# Sheet1.net
KiCad netlist of a schematic drawn in Altium Designer
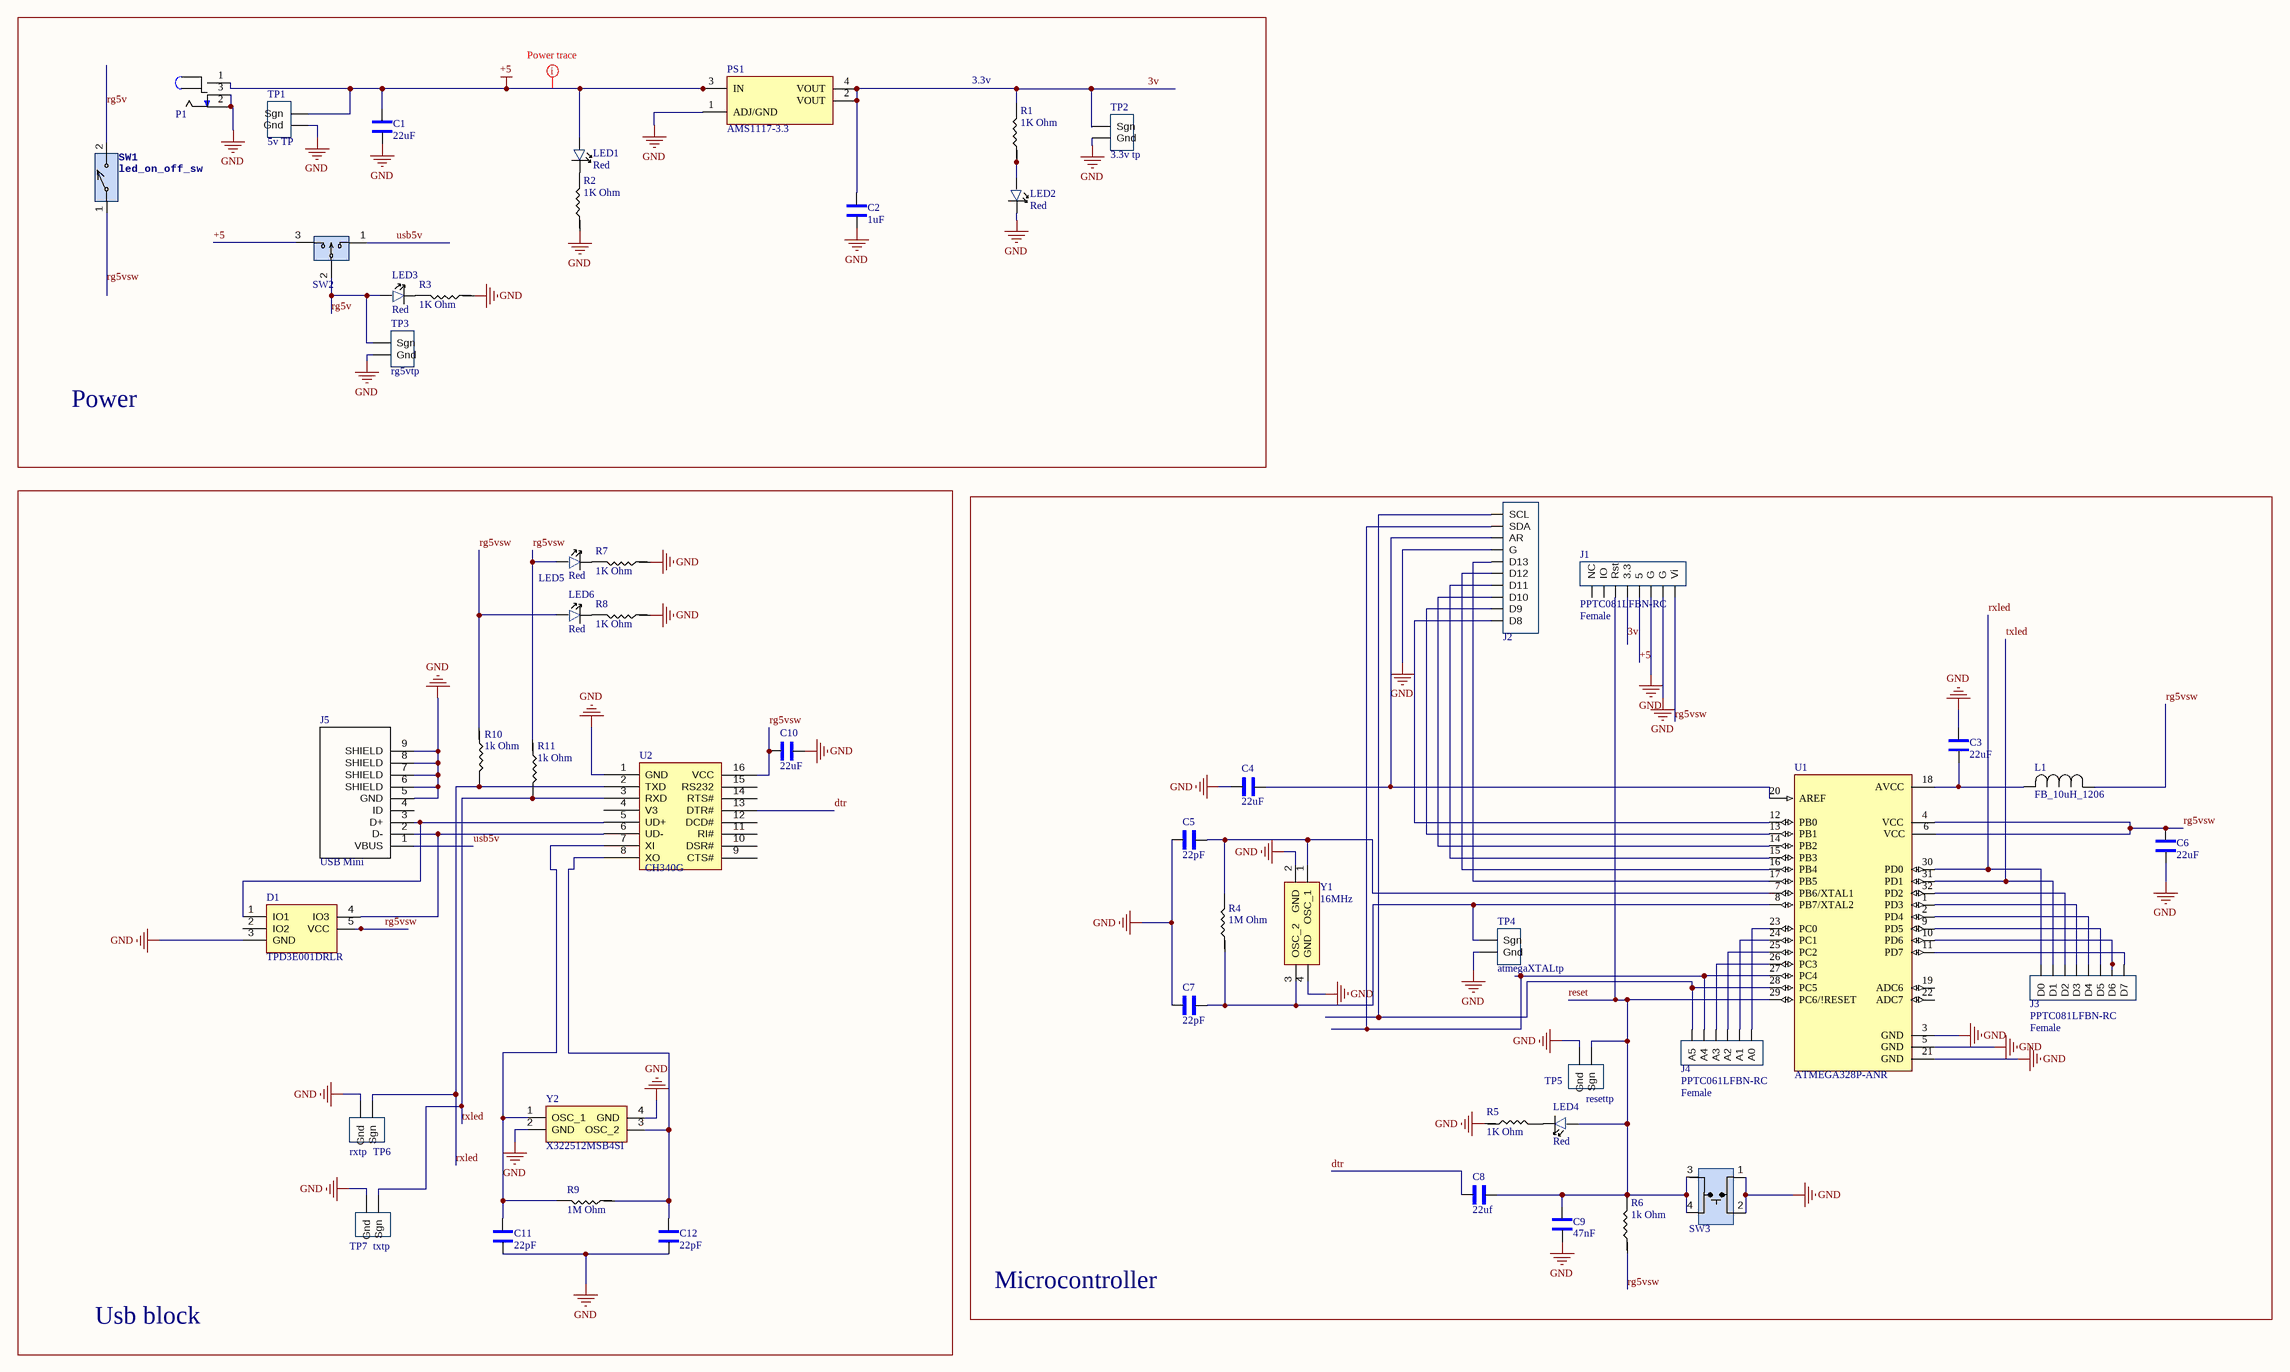
[diagram p0: Sheet1.SchDoc]

(export (version "E")
  (design (tool "Eeschema 10.0.6"))
  (components
    (comp (ref "C1")
      (value "22uF")
      (footprint "1206_Passive_Capacitor")
      (description "22uF ±10% 25V X5R 1206 Multilayer Ceramic Capacitors MLCC - SMD/SMT RoHS")
      (fields (field (name "MFR PART #") "CL31A226KAHNNNE") (field (name "LCSC PART#") "C12891"))
      (libsource (lib "ECEN5730Lib_2023_05_DS") (part "C_22uF_1206"))
    )
    (comp (ref "C2")
      (value "1uF")
      (footprint "1206_Passive_Capacitor")
      (description "MULTILAYER CERAMIC CAPACITORS MLCC - SMD/SMT 1UF 50V 1206 ROHS")
      (fields (field (name "MFR PART #") "CL31B105KBHNNNE") (field (name "LCSC PART#") "C1848"))
      (libsource (lib "ECEN5730Lib_2023_05_DS") (part "C_1uF_1206"))
    )
    (comp (ref "C3")
      (value "22uF")
      (footprint "1206_Passive_Capacitor")
      (description "22uF ±10% 25V X5R 1206 Multilayer Ceramic Capacitors MLCC - SMD/SMT RoHS")
      (fields (field (name "MFR PART #") "CL31A226KAHNNNE") (field (name "LCSC PART#") "C12891"))
      (libsource (lib "ECEN5730Lib_2023_05_DS") (part "C_22uF_1206"))
    )
    (comp (ref "C4")
      (value "22uF")
      (footprint "1206_Passive_Capacitor")
      (description "22uF ±10% 25V X5R 1206 Multilayer Ceramic Capacitors MLCC - SMD/SMT RoHS")
      (fields (field (name "MFR PART #") "CL31A226KAHNNNE") (field (name "LCSC PART#") "C12891"))
      (libsource (lib "ECEN5730Lib_2023_05_DS") (part "C_22uF_1206"))
    )
    (comp (ref "C5")
      (value "22pF")
      (footprint "1206_Passive_Capacitor")
      (description "22pF ±5% 1kV C0G 1206 Multilayer Ceramic Capacitors MLCC - SMD/SMT RoHS")
      (fields (field (name "LCSC PART#") "C107174") (field (name "MFR PART #") "CC1206JKNPOCBN220"))
      (libsource (lib "ECEN5730Lib_2023_05_DS") (part "C_22pF_1206"))
    )
    (comp (ref "C6")
      (value "22uF")
      (footprint "1206_Passive_Capacitor")
      (description "22uF ±10% 25V X5R 1206 Multilayer Ceramic Capacitors MLCC - SMD/SMT RoHS")
      (fields (field (name "MFR PART #") "CL31A226KAHNNNE") (field (name "LCSC PART#") "C12891"))
      (libsource (lib "ECEN5730Lib_2023_05_DS") (part "C_22uF_1206"))
    )
    (comp (ref "C7")
      (value "22pF")
      (footprint "1206_Passive_Capacitor")
      (description "22pF ±5% 1kV C0G 1206 Multilayer Ceramic Capacitors MLCC - SMD/SMT RoHS")
      (fields (field (name "LCSC PART#") "C107174") (field (name "MFR PART #") "CC1206JKNPOCBN220"))
      (libsource (lib "ECEN5730Lib_2023_05_DS") (part "C_22pF_1206"))
    )
    (comp (ref "C8")
      (value "22uf")
      (footprint "1206_Passive_Capacitor")
      (description "MULTILAYER CERAMIC CAPACITORS MLCC - SMD/SMT 1UF 50V 1206 ROHS")
      (fields (field (name "MFR PART #") "CL31B105KBHNNNE") (field (name "LCSC PART#") "C1848"))
      (libsource (lib "ECEN5730Lib_2023_05_DS") (part "C_1uF_1206"))
    )
    (comp (ref "C9")
      (value "47nF")
      (footprint "1206_Passive_Capacitor")
      (description "47nF ±5% 50V C0G 1206 Multilayer Ceramic Capacitors MLCC - SMD/SMT RoHS")
      (fields (field (name "LCSC PART#") "C21812") (field (name "MFR PART #") "GRM31M5C1H473JA01L"))
      (libsource (lib "ECEN5730Lib_2023_05_DS") (part "C_47nF_1206"))
    )
    (comp (ref "C10")
      (value "22uF")
      (footprint "1206_Passive_Capacitor")
      (description "22uF ±10% 25V X5R 1206 Multilayer Ceramic Capacitors MLCC - SMD/SMT RoHS")
      (fields (field (name "MFR PART #") "CL31A226KAHNNNE") (field (name "LCSC PART#") "C12891"))
      (libsource (lib "ECEN5730Lib_2023_05_DS") (part "C_22uF_1206"))
    )
    (comp (ref "C11")
      (value "22pF")
      (footprint "1206_Passive_Capacitor")
      (description "22pF ±5% 1kV C0G 1206 Multilayer Ceramic Capacitors MLCC - SMD/SMT RoHS")
      (fields (field (name "LCSC PART#") "C107174") (field (name "MFR PART #") "CC1206JKNPOCBN220"))
      (libsource (lib "ECEN5730Lib_2023_05_DS") (part "C_22pF_1206"))
    )
    (comp (ref "C12")
      (value "22pF")
      (footprint "1206_Passive_Capacitor")
      (description "22pF ±5% 1kV C0G 1206 Multilayer Ceramic Capacitors MLCC - SMD/SMT RoHS")
      (fields (field (name "LCSC PART#") "C107174") (field (name "MFR PART #") "CC1206JKNPOCBN220"))
      (libsource (lib "ECEN5730Lib_2023_05_DS") (part "C_22pF_1206"))
    )
    (comp (ref "D1")
      (value "TPD3E001DRLR")
      (footprint "SOTFL50P160X60-5N")
      (description "Low-Capacitance 3-Channel +/-15KV ESD-Protection Array for High-Speed Data Interfaces")
      (fields (field (name "MOUSER PART NUMBER") "595-TPD3E001DRLR"))
      (libsource (lib "TPD3E001DRLR") (part "TPD3E001DRLR"))
    )
    (comp (ref "J1")
      (value "PPTC081LFBN-RC")
      (footprint "8_PIN_ARD-PWR_100MIL")
      (description "8 Position Header Connector 0.100\" (2.54mm) Through Hole Tin")
      (fields (field (name "LCSC PART#") "C27438") (field (name "ALTIUM_VALUE") "Female"))
      (libsource (lib "ECEN5730Lib_2023_05_DS") (part "JF_8_PIN_FEMA_ARD-Pwr"))
    )
    (comp (ref "J2")
      (value "PPTC101LFBN-RC")
      (footprint "10_PIN_ARDUINO_100MIL")
      (description "10 Position Header Connector 0.100\" (2.54mm) Through Hole Tin")
      (fields (field (name "LCSC PART#") "C225507"))
      (libsource (lib "ECEN5730Lib_2023_05_DS") (part "JF_10_PIN_FEMA_ARDUINO"))
    )
    (comp (ref "J3")
      (value "PPTC081LFBN-RC")
      (footprint "8_PIN_ARD-DIG_100MIL")
      (description "8 Position Header Connector 0.100\" (2.54mm) Through Hole Tin")
      (fields (field (name "LCSC PART#") "C27438") (field (name "ALTIUM_VALUE") "Female"))
      (libsource (lib "ECEN5730Lib_2023_05_DS") (part "JF_8_PIN_FEMA_ARD-Dig"))
    )
    (comp (ref "J4")
      (value "PPTC061LFBN-RC")
      (footprint "6_PIN_ARD-Analog_100mil")
      (description "6 Position Header Connector 0.100\" (2.54mm) Through Hole Tin")
      (fields (field (name "LCSC PART#") "C40877") (field (name "ALTIUM_VALUE") "Female"))
      (libsource (lib "ECEN5730Lib_2023_05_DS") (part "JF_6_PIN_FEMA_ARD-Anolog"))
    )
    (comp (ref "J5")
      (value "USB Mini")
      (footprint "USB_MINI_B")
      (description "Through Hole USB Connectors RoHS")
      (fields (field (name "LCSC PART#") "C46398") (field (name "MFR PART #") "920-462A2021D10102"))
      (libsource (lib "ECEN5730Lib_2023_05_DS") (part "J_USB_B_Mini"))
    )
    (comp (ref "L1")
      (value "FB_10uH_1206")
      (footprint "AIML-1206_ABR-M")
      (description "25mA 10uH ±10% 800mΩ 1206  Inductors (SMD) ROHS")
      (fields (field (name "MFR PART #") "CMI321609X100KT") (field (name "LCSC PART#") "C1051"))
      (libsource (lib "ECEN5730Lib_2023_05_DS") (part "FB_10uH_1206"))
    )
    (comp (ref "LED1")
      (value "Red")
      (footprint "LED_1206")
      (description "Red 621~631nm 1206 Light Emitting Diodes (LED) RoHS")
      (fields (field (name "MFR PART #") "15-21/R6C-FQ1R1B/2T") (field (name "LCSC PART#") "C93133"))
      (libsource (lib "ECEN5730Lib_2023_05_DS") (part "LED_RED_1206"))
    )
    (comp (ref "LED2")
      (value "Red")
      (footprint "LED_1206")
      (description "Red 621~631nm 1206 Light Emitting Diodes (LED) RoHS")
      (fields (field (name "MFR PART #") "15-21/R6C-FQ1R1B/2T") (field (name "LCSC PART#") "C93133"))
      (libsource (lib "ECEN5730Lib_2023_05_DS") (part "LED_RED_1206"))
    )
    (comp (ref "LED3")
      (value "Red")
      (footprint "LED_1206")
      (description "Red 621~631nm 1206 Light Emitting Diodes (LED) RoHS")
      (fields (field (name "MFR PART #") "15-21/R6C-FQ1R1B/2T") (field (name "LCSC PART#") "C93133"))
      (libsource (lib "ECEN5730Lib_2023_05_DS") (part "LED_RED_1206"))
    )
    (comp (ref "LED4")
      (value "Red")
      (footprint "LED_1206")
      (description "Red 621~631nm 1206 Light Emitting Diodes (LED) RoHS")
      (fields (field (name "MFR PART #") "15-21/R6C-FQ1R1B/2T") (field (name "LCSC PART#") "C93133"))
      (libsource (lib "ECEN5730Lib_2023_05_DS") (part "LED_RED_1206"))
    )
    (comp (ref "LED5")
      (value "Red")
      (footprint "LED_1206")
      (description "Red 621~631nm 1206 Light Emitting Diodes (LED) RoHS")
      (fields (field (name "MFR PART #") "15-21/R6C-FQ1R1B/2T") (field (name "LCSC PART#") "C93133"))
      (libsource (lib "ECEN5730Lib_2023_05_DS") (part "LED_RED_1206"))
    )
    (comp (ref "LED6")
      (value "Red")
      (footprint "LED_1206")
      (description "Red 621~631nm 1206 Light Emitting Diodes (LED) RoHS")
      (fields (field (name "MFR PART #") "15-21/R6C-FQ1R1B/2T") (field (name "LCSC PART#") "C93133"))
      (libsource (lib "ECEN5730Lib_2023_05_DS") (part "LED_RED_1206"))
    )
    (comp (ref "P1")
      (value "Power Jack")
      (footprint "Power_Jack")
      (description "Power Barrel Connector Jack 2.10mm ID (0.083\"), 5.50mm OD (0.217\") Through Hole, Right Angle")
      (fields (field (name "MFR PART #") "PJ-102A") (field (name "LCSC PART#") "C136744"))
      (libsource (lib "ECEN5730Lib_2023_05_DS") (part "P_Power Jack"))
    )
    (comp (ref "PS1")
      (value "AMS1117-3.3")
      (footprint "LDO")
      (description "LOW DROPOUT REGULATORS(LDO) POSITIVE FIXED 1.3V @ 800MA 15V 3.3V 1A SOT-223 ROHS")
      (fields (field (name "LCSC PART#") "C6186"))
      (libsource (lib "ECEN5730Lib_2023_05_DS") (part "PS_AMS_LDO_3v3"))
    )
    (comp (ref "R1")
      (value "1K Ohm")
      (footprint "1206_Passive_Resitor")
      (description "CHIP RESISTOR - SURFACE MOUNT 1KOHMS ±1% 1/4W 1206 ROHS")
      (fields (field (name "MFR PART #") "RNCP1206FTD1K00CT") (field (name "LCSC PART#") "C4410"))
      (libsource (lib "ECEN5730Lib_2023_05_DS") (part "R_1K_1206"))
    )
    (comp (ref "R2")
      (value "1K Ohm")
      (footprint "1206_Passive_Resitor")
      (description "CHIP RESISTOR - SURFACE MOUNT 1KOHMS ±1% 1/4W 1206 ROHS")
      (fields (field (name "MFR PART #") "RNCP1206FTD1K00CT") (field (name "LCSC PART#") "C4410"))
      (libsource (lib "ECEN5730Lib_2023_05_DS") (part "R_1K_1206"))
    )
    (comp (ref "R3")
      (value "1K Ohm")
      (footprint "1206_Passive_Resitor")
      (description "CHIP RESISTOR - SURFACE MOUNT 1KOHMS ±1% 1/4W 1206 ROHS")
      (fields (field (name "MFR PART #") "RNCP1206FTD1K00CT") (field (name "LCSC PART#") "C4410"))
      (libsource (lib "ECEN5730Lib_2023_05_DS") (part "R_1K_1206"))
    )
    (comp (ref "R4")
      (value "1M Ohm")
      (footprint "1206_Passive_Resitor")
      (description "CHIP RESISTOR - SURFACE MOUNT 1MOHMS ±1% 1/4W 1206 ROHS")
      (fields (field (name "MFR PART #") "RMCF1206JT1M00") (field (name "LCSC PART#") "C17927"))
      (libsource (lib "ECEN5730Lib_2023_05_DS") (part "R_1M_1206"))
    )
    (comp (ref "R5")
      (value "1K Ohm")
      (footprint "1206_Passive_Resitor")
      (description "CHIP RESISTOR - SURFACE MOUNT 1KOHMS ±1% 1/4W 1206 ROHS")
      (fields (field (name "MFR PART #") "RNCP1206FTD1K00CT") (field (name "LCSC PART#") "C4410"))
      (libsource (lib "ECEN5730Lib_2023_05_DS") (part "R_1K_1206"))
    )
    (comp (ref "R6")
      (value "1k Ohm")
      (footprint "1206_Passive_Resitor")
      (description "10 kOhms ±5% 0.25W, 1/4W Chip Resistor 1206 (3216 Metric) Automotive AEC-Q200 Thick Film")
      (fields (field (name "MFR PART #") "RMCF1206FT10K0") (field (name "LCSC PART#") "C17902"))
      (libsource (lib "ECEN5730Lib_2023_05_DS") (part "R_10KOhm_1206"))
    )
    (comp (ref "R7")
      (value "1K Ohm")
      (footprint "1206_Passive_Resitor")
      (description "CHIP RESISTOR - SURFACE MOUNT 1KOHMS ±1% 1/4W 1206 ROHS")
      (fields (field (name "MFR PART #") "RNCP1206FTD1K00CT") (field (name "LCSC PART#") "C4410"))
      (libsource (lib "ECEN5730Lib_2023_05_DS") (part "R_1K_1206"))
    )
    (comp (ref "R8")
      (value "1K Ohm")
      (footprint "1206_Passive_Resitor")
      (description "CHIP RESISTOR - SURFACE MOUNT 1KOHMS ±1% 1/4W 1206 ROHS")
      (fields (field (name "MFR PART #") "RNCP1206FTD1K00CT") (field (name "LCSC PART#") "C4410"))
      (libsource (lib "ECEN5730Lib_2023_05_DS") (part "R_1K_1206"))
    )
    (comp (ref "R9")
      (value "1M Ohm")
      (footprint "1206_Passive_Resitor")
      (description "CHIP RESISTOR - SURFACE MOUNT 1MOHMS ±1% 1/4W 1206 ROHS")
      (fields (field (name "MFR PART #") "RMCF1206JT1M00") (field (name "LCSC PART#") "C17927"))
      (libsource (lib "ECEN5730Lib_2023_05_DS") (part "R_1M_1206"))
    )
    (comp (ref "R10")
      (value "1k Ohm")
      (footprint "1206_Passive_Resitor")
      (description "CHIP RESISTOR - SURFACE MOUNT 1MOHMS ±1% 1/4W 1206 ROHS")
      (fields (field (name "MFR PART #") "RMCF1206JT1M00") (field (name "LCSC PART#") "C17927"))
      (libsource (lib "ECEN5730Lib_2023_05_DS") (part "R_1M_1206"))
    )
    (comp (ref "R11")
      (value "1k Ohm")
      (footprint "1206_Passive_Resitor")
      (description "CHIP RESISTOR - SURFACE MOUNT 1MOHMS ±1% 1/4W 1206 ROHS")
      (fields (field (name "MFR PART #") "RMCF1206JT1M00") (field (name "LCSC PART#") "C17927"))
      (libsource (lib "ECEN5730Lib_2023_05_DS") (part "R_1M_1206"))
    )
    (comp (ref "SW1")
      (value "led_on_off_sw")
      (footprint "2Pin-Header-Conn")
      (description "2Pin Header")
      (fields (field (name "LCSC PART#") "C124375"))
      (libsource (lib "ECEN5730Lib_2023_05_DS") (part "SW_2Pin_100mil_Switch"))
    )
    (comp (ref "SW2")
      (value "PREC003SAAN-RC")
      (footprint "3_PIN_100mil")
      (description "Connector Header Through Hole 3 position 0.100\" (2.54mm)")
      (fields (field (name "LCSC PART#") "C49257"))
      (libsource (lib "ECEN5730Lib_2023_05_DS") (part "SW_3Pin_100mil_Switch"))
    )
    (comp (ref "SW3")
      (value "TL3305AF160QG")
      (footprint "Switch_JLC")
      (description "Tactile Switch SPST-NO Top Actuated Surface Mount")
      (fields (field (name "MFR PART #") "KH-4.5X4.5X4.3H-STM") (field (name "LCSC PART#") "C2837550"))
      (libsource (lib "ECEN5730Lib_2023_05_DS") (part "SW_Push_Button_JLC"))
    )
    (comp (ref "TP1")
      (value "5v TP")
      (footprint "TP10x_Probe")
      (description "Test Point 300 mil centers")
      (libsource (lib "ECEN5730Lib_2023_05_DS") (part "TP_10x_Probe"))
    )
    (comp (ref "TP2")
      (value "3.3v tp")
      (footprint "TP10x_Probe")
      (description "Test Point 300 mil centers")
      (libsource (lib "") (part "TP_10x_Probe_1"))
    )
    (comp (ref "TP3")
      (value "rg5vtp")
      (footprint "TP10x_Probe")
      (description "Test Point 300 mil centers")
      (libsource (lib "") (part "TP_10x_Probe_1"))
    )
    (comp (ref "TP4")
      (value "atmegaXTALtp")
      (footprint "TP10x_Probe")
      (description "Test Point 300 mil centers")
      (libsource (lib "") (part "TP_10x_Probe_1"))
    )
    (comp (ref "TP5")
      (value "resettp")
      (footprint "TP10x_Probe")
      (description "Test Point 300 mil centers")
      (libsource (lib "ECEN5730Lib_2023_05_DS") (part "TP_10x_Probe"))
    )
    (comp (ref "TP6")
      (value "rxtp")
      (footprint "TP10x_Probe")
      (description "Test Point 300 mil centers")
      (libsource (lib "ECEN5730Lib_2023_05_DS") (part "TP_10x_Probe"))
    )
    (comp (ref "TP7")
      (value "txtp")
      (footprint "TP10x_Probe")
      (description "Test Point 300 mil centers")
      (libsource (lib "ECEN5730Lib_2023_05_DS") (part "TP_10x_Probe"))
    )
    (comp (ref "U1")
      (value "ATMEGA328P-ANR")
      (footprint "ATMega328P")
      (description "AVR AVR® ATmega Microcontroller IC 8-Bit 20MHz 32KB (16K x 16) FLASH 32-TQFP (7x7)")
      (fields (field (name "MFR PART #") "ATMEGA328P-AU") (field (name "LCSC PART#") "C14877"))
      (libsource (lib "ECEN5730Lib_2023_05_DS") (part "U_ATMega328P"))
    )
    (comp (ref "U2")
      (value "CH340G")
      (footprint "USB to serial")
      (description "Transceiver USB 2.0 2Mbps SOP-16_150mil USB ICs RoHS")
      (fields (field (name "LCSC PART#") "C14267"))
      (libsource (lib "ECEN5730Lib_2023_05_DS") (part "U_USBtoSerial"))
    )
    (comp (ref "Y1")
      (value "16MHz")
      (footprint "Crystal resonator")
      (description "±10ppm 16000000Hz -40℃~85℃ 贴片无源晶振 60Ω 9pF SMD3225-4P Crystals ROHS")
      (fields (field (name "LCSC PART#") "C13738") (field (name "MFR PART #") "X322516MLB4SI"))
      (libsource (lib "ECEN5730Lib_2023_05_DS") (part "X_16Mhz_Res"))
    )
    (comp (ref "Y2")
      (value "X322512MSB4SI")
      (footprint "Crystal resonator")
      (description "SMD Crystal Resonators 12MHz ±10ppm SMD-3225_4P RoHS")
      (fields (field (name "LCSC PART#") "C9002"))
      (libsource (lib "ECEN5730Lib_2023_05_DS") (part "X_12MHz_Res"))
    )
  )
  (nets
    (net (code "1") (name "+5") (class "Default")
      (node (ref "C1") (pin "2") (pinfunction "2_2") (pintype "passive"))
      (node (ref "J1") (pin "5") (pinfunction "5_5") (pintype "passive"))
      (node (ref "LED1") (pin "1") (pinfunction "1_1") (pintype "passive"))
      (node (ref "P1") (pin "1") (pinfunction "1_1") (pintype "power_in"))
      (node (ref "PS1") (pin "3") (pinfunction "IN_3") (pintype "power_in"))
      (node (ref "SW2") (pin "3") (pinfunction "3_3") (pintype "passive"))
      (node (ref "TP1") (pin "1") (pinfunction "Sgn_1") (pintype "passive"))
    )
    (net (code "2") (name "/3v") (class "Default")
      (node (ref "C2") (pin "2") (pinfunction "2_2") (pintype "passive"))
      (node (ref "J1") (pin "4") (pinfunction "3.3_4") (pintype "passive"))
      (node (ref "PS1") (pin "2") (pinfunction "VOUT_2") (pintype "power_in"))
      (node (ref "PS1") (pin "4") (pinfunction "VOUT_4") (pintype "power_in"))
      (node (ref "R1") (pin "2") (pinfunction "2_2") (pintype "passive"))
      (node (ref "TP2") (pin "1") (pinfunction "Sgn_1") (pintype "passive"))
    )
    (net (code "3") (name "/dtr") (class "Default")
      (node (ref "C8") (pin "1") (pinfunction "1_1") (pintype "passive"))
      (node (ref "U2") (pin "13") (pinfunction "DTR#_13") (pintype "passive"))
    )
    (net (code "4") (name "/reset") (class "Default")
      (node (ref "C8") (pin "2") (pinfunction "2_2") (pintype "passive"))
      (node (ref "C9") (pin "2") (pinfunction "2_2") (pintype "passive"))
      (node (ref "J1") (pin "3") (pinfunction "Rst_3") (pintype "passive"))
      (node (ref "LED4") (pin "1") (pinfunction "1_1") (pintype "passive"))
      (node (ref "R6") (pin "2") (pinfunction "2_2") (pintype "passive"))
      (node (ref "SW3") (pin "3") (pinfunction "3_3") (pintype "passive"))
      (node (ref "SW3") (pin "4") (pinfunction "4_4") (pintype "passive"))
      (node (ref "TP5") (pin "1") (pinfunction "Sgn_1") (pintype "passive"))
      (node (ref "U1") (pin "29") (pinfunction "PC6/!RESET_29") (pintype "bidirectional"))
    )
    (net (code "5") (name "/rg5v") (class "Default")
      (node (ref "LED3") (pin "1") (pinfunction "1_1") (pintype "passive"))
      (node (ref "SW1") (pin "2") (pinfunction "2_2") (pintype "passive"))
      (node (ref "SW2") (pin "2") (pinfunction "2_2") (pintype "passive"))
      (node (ref "TP3") (pin "1") (pinfunction "Sgn_1") (pintype "passive"))
    )
    (net (code "6") (name "/rg5vsw") (class "Default")
      (node (ref "C10") (pin "1") (pinfunction "1_1") (pintype "passive"))
      (node (ref "C6") (pin "2") (pinfunction "2_2") (pintype "passive"))
      (node (ref "D1") (pin "5") (pinfunction "VCC_5") (pintype "passive"))
      (node (ref "J1") (pin "8") (pinfunction "Vi_8") (pintype "passive"))
      (node (ref "L1") (pin "1") (pinfunction "1_1") (pintype "passive"))
      (node (ref "LED5") (pin "1") (pinfunction "1_1") (pintype "passive"))
      (node (ref "LED6") (pin "1") (pinfunction "1_1") (pintype "passive"))
      (node (ref "R10") (pin "1") (pinfunction "1_1") (pintype "passive"))
      (node (ref "R11") (pin "1") (pinfunction "1_1") (pintype "passive"))
      (node (ref "R6") (pin "1") (pinfunction "1_1") (pintype "passive"))
      (node (ref "SW1") (pin "1") (pinfunction "1_1") (pintype "passive"))
      (node (ref "U1") (pin "4") (pinfunction "VCC_4") (pintype "power_in"))
      (node (ref "U1") (pin "6") (pinfunction "VCC_6") (pintype "power_in"))
      (node (ref "U2") (pin "16") (pinfunction "VCC_16") (pintype "passive"))
    )
    (net (code "7") (name "/rxled") (class "Default")
      (node (ref "J3") (pin "8") (pinfunction "D0_8") (pintype "passive"))
      (node (ref "R10") (pin "2") (pinfunction "2_2") (pintype "passive"))
      (node (ref "TP6") (pin "1") (pinfunction "Sgn_1") (pintype "passive"))
      (node (ref "U1") (pin "30") (pinfunction "PD0_30") (pintype "bidirectional"))
      (node (ref "U2") (pin "2") (pinfunction "TXD_2") (pintype "passive"))
    )
    (net (code "8") (name "/txled") (class "Default")
      (node (ref "J3") (pin "7") (pinfunction "D1_7") (pintype "passive"))
      (node (ref "R11") (pin "2") (pinfunction "2_2") (pintype "passive"))
      (node (ref "TP7") (pin "1") (pinfunction "Sgn_1") (pintype "passive"))
      (node (ref "U1") (pin "31") (pinfunction "PD1_31") (pintype "bidirectional"))
      (node (ref "U2") (pin "3") (pinfunction "RXD_3") (pintype "passive"))
    )
    (net (code "9") (name "/usb5v") (class "Default")
      (node (ref "J5") (pin "1") (pinfunction "VBUS_1") (pintype "passive"))
      (node (ref "SW2") (pin "1") (pinfunction "1_1") (pintype "passive"))
    )
    (net (code "10") (name "GND") (class "Default")
      (node (ref "C1") (pin "1") (pinfunction "1_1") (pintype "passive"))
      (node (ref "C10") (pin "2") (pinfunction "2_2") (pintype "passive"))
      (node (ref "C11") (pin "1") (pinfunction "1_1") (pintype "passive"))
      (node (ref "C12") (pin "1") (pinfunction "1_1") (pintype "passive"))
      (node (ref "C2") (pin "1") (pinfunction "1_1") (pintype "passive"))
      (node (ref "C3") (pin "2") (pinfunction "2_2") (pintype "passive"))
      (node (ref "C4") (pin "2") (pinfunction "2_2") (pintype "passive"))
      (node (ref "C5") (pin "1") (pinfunction "1_1") (pintype "passive"))
      (node (ref "C6") (pin "1") (pinfunction "1_1") (pintype "passive"))
      (node (ref "C7") (pin "1") (pinfunction "1_1") (pintype "passive"))
      (node (ref "C9") (pin "1") (pinfunction "1_1") (pintype "passive"))
      (node (ref "D1") (pin "3") (pinfunction "GND_3") (pintype "passive"))
      (node (ref "J1") (pin "6") (pinfunction "G_6") (pintype "passive"))
      (node (ref "J1") (pin "7") (pinfunction "G_7") (pintype "passive"))
      (node (ref "J2") (pin "4") (pinfunction "G_4") (pintype "passive"))
      (node (ref "J5") (pin "5") (pinfunction "GND_5") (pintype "passive"))
      (node (ref "J5") (pin "6") (pinfunction "SHIELD_6") (pintype "passive"))
      (node (ref "J5") (pin "7") (pinfunction "SHIELD_7") (pintype "passive"))
      (node (ref "J5") (pin "8") (pinfunction "SHIELD_8") (pintype "passive"))
      (node (ref "J5") (pin "9") (pinfunction "SHIELD_9") (pintype "passive"))
      (node (ref "LED2") (pin "2") (pinfunction "2_2") (pintype "passive"))
      (node (ref "P1") (pin "2") (pinfunction "2_2") (pintype "power_in"))
      (node (ref "P1") (pin "3") (pinfunction "3_3") (pintype "power_in"))
      (node (ref "PS1") (pin "1") (pinfunction "ADJ/GND_1") (pintype "passive"))
      (node (ref "R2") (pin "1") (pinfunction "1_1") (pintype "passive"))
      (node (ref "R3") (pin "1") (pinfunction "1_1") (pintype "passive"))
      (node (ref "R5") (pin "1") (pinfunction "1_1") (pintype "passive"))
      (node (ref "R7") (pin "1") (pinfunction "1_1") (pintype "passive"))
      (node (ref "R8") (pin "1") (pinfunction "1_1") (pintype "passive"))
      (node (ref "SW3") (pin "1") (pinfunction "1_1") (pintype "passive"))
      (node (ref "SW3") (pin "2") (pinfunction "2_2") (pintype "passive"))
      (node (ref "TP1") (pin "2") (pinfunction "Gnd_2") (pintype "passive"))
      (node (ref "TP2") (pin "2") (pinfunction "Gnd_2") (pintype "passive"))
      (node (ref "TP3") (pin "2") (pinfunction "Gnd_2") (pintype "passive"))
      (node (ref "TP4") (pin "2") (pinfunction "Gnd_2") (pintype "passive"))
      (node (ref "TP5") (pin "2") (pinfunction "Gnd_2") (pintype "passive"))
      (node (ref "TP6") (pin "2") (pinfunction "Gnd_2") (pintype "passive"))
      (node (ref "TP7") (pin "2") (pinfunction "Gnd_2") (pintype "passive"))
      (node (ref "U1") (pin "21") (pinfunction "GND_21") (pintype "power_in"))
      (node (ref "U1") (pin "3") (pinfunction "GND_3") (pintype "power_in"))
      (node (ref "U1") (pin "5") (pinfunction "GND_5") (pintype "power_in"))
      (node (ref "U2") (pin "1") (pinfunction "GND_1") (pintype "passive"))
      (node (ref "Y1") (pin "2") (pinfunction "GND_2") (pintype "passive"))
      (node (ref "Y1") (pin "4") (pinfunction "GND_4") (pintype "passive"))
      (node (ref "Y2") (pin "2") (pinfunction "GND_2") (pintype "passive"))
      (node (ref "Y2") (pin "4") (pinfunction "GND_4") (pintype "passive"))
    )
    (net (code "11") (name "Net-(D1-IO1)") (class "Default")
      (node (ref "D1") (pin "1") (pinfunction "IO1_1") (pintype "passive"))
      (node (ref "J5") (pin "3") (pinfunction "D+_3") (pintype "passive"))
      (node (ref "U2") (pin "5") (pinfunction "UD+_5") (pintype "passive"))
    )
    (net (code "12") (name "Net-(D1-IO3)") (class "Default")
      (node (ref "D1") (pin "4") (pinfunction "IO3_4") (pintype "passive"))
      (node (ref "J5") (pin "2") (pinfunction "D-_2") (pintype "passive"))
      (node (ref "U2") (pin "6") (pinfunction "UD-_6") (pintype "passive"))
    )
    (net (code "13") (name "Net-(J2-AR)") (class "Default")
      (node (ref "C4") (pin "1") (pinfunction "1_1") (pintype "passive"))
      (node (ref "J2") (pin "3") (pinfunction "AR_3") (pintype "passive"))
      (node (ref "U1") (pin "20") (pinfunction "AREF_20") (pintype "input"))
    )
    (net (code "14") (name "Net-(J2-D8)") (class "Default")
      (node (ref "J2") (pin "10") (pinfunction "D8_10") (pintype "passive"))
      (node (ref "U1") (pin "12") (pinfunction "PB0_12") (pintype "bidirectional"))
    )
    (net (code "15") (name "Net-(J2-D9)") (class "Default")
      (node (ref "J2") (pin "9") (pinfunction "D9_9") (pintype "passive"))
      (node (ref "U1") (pin "13") (pinfunction "PB1_13") (pintype "bidirectional"))
    )
    (net (code "16") (name "Net-(J2-D10)") (class "Default")
      (node (ref "J2") (pin "8") (pinfunction "D10_8") (pintype "passive"))
      (node (ref "U1") (pin "14") (pinfunction "PB2_14") (pintype "bidirectional"))
    )
    (net (code "17") (name "Net-(J2-D11)") (class "Default")
      (node (ref "J2") (pin "7") (pinfunction "D11_7") (pintype "passive"))
      (node (ref "U1") (pin "15") (pinfunction "PB3_15") (pintype "bidirectional"))
    )
    (net (code "18") (name "Net-(J2-D12)") (class "Default")
      (node (ref "J2") (pin "6") (pinfunction "D12_6") (pintype "passive"))
      (node (ref "U1") (pin "16") (pinfunction "PB4_16") (pintype "bidirectional"))
    )
    (net (code "19") (name "Net-(J2-D13)") (class "Default")
      (node (ref "J2") (pin "5") (pinfunction "D13_5") (pintype "passive"))
      (node (ref "U1") (pin "17") (pinfunction "PB5_17") (pintype "bidirectional"))
    )
    (net (code "20") (name "Net-(J2-SCL)") (class "Default")
      (node (ref "J2") (pin "1") (pinfunction "SCL_1") (pintype "passive"))
      (node (ref "J4") (pin "6") (pinfunction "A5_6") (pintype "passive"))
      (node (ref "U1") (pin "28") (pinfunction "PC5_28") (pintype "bidirectional"))
    )
    (net (code "21") (name "Net-(J2-SDA)") (class "Default")
      (node (ref "J2") (pin "2") (pinfunction "SDA_2") (pintype "passive"))
      (node (ref "J4") (pin "5") (pinfunction "A4_5") (pintype "passive"))
      (node (ref "U1") (pin "27") (pinfunction "PC4_27") (pintype "bidirectional"))
    )
    (net (code "22") (name "Net-(J3-D2)") (class "Default")
      (node (ref "J3") (pin "6") (pinfunction "D2_6") (pintype "passive"))
      (node (ref "U1") (pin "32") (pinfunction "PD2_32") (pintype "bidirectional"))
    )
    (net (code "23") (name "Net-(J3-D3)") (class "Default")
      (node (ref "J3") (pin "5") (pinfunction "D3_5") (pintype "passive"))
      (node (ref "U1") (pin "1") (pinfunction "PD3_1") (pintype "bidirectional"))
    )
    (net (code "24") (name "Net-(J3-D4)") (class "Default")
      (node (ref "J3") (pin "4") (pinfunction "D4_4") (pintype "passive"))
      (node (ref "U1") (pin "2") (pinfunction "PD4_2") (pintype "bidirectional"))
    )
    (net (code "25") (name "Net-(J3-D5)") (class "Default")
      (node (ref "J3") (pin "3") (pinfunction "D5_3") (pintype "passive"))
      (node (ref "U1") (pin "9") (pinfunction "PD5_9") (pintype "bidirectional"))
    )
    (net (code "26") (name "Net-(J3-D6)") (class "Default")
      (node (ref "J3") (pin "2") (pinfunction "D6_2") (pintype "passive"))
      (node (ref "U1") (pin "10") (pinfunction "PD6_10") (pintype "bidirectional"))
    )
    (net (code "27") (name "Net-(J3-D7)") (class "Default")
      (node (ref "J3") (pin "1") (pinfunction "D7_1") (pintype "passive"))
      (node (ref "U1") (pin "11") (pinfunction "PD7_11") (pintype "bidirectional"))
    )
    (net (code "28") (name "Net-(J4-A0)") (class "Default")
      (node (ref "J4") (pin "1") (pinfunction "A0_1") (pintype "passive"))
      (node (ref "U1") (pin "23") (pinfunction "PC0_23") (pintype "bidirectional"))
    )
    (net (code "29") (name "Net-(J4-A1)") (class "Default")
      (node (ref "J4") (pin "2") (pinfunction "A1_2") (pintype "passive"))
      (node (ref "U1") (pin "24") (pinfunction "PC1_24") (pintype "bidirectional"))
    )
    (net (code "30") (name "Net-(J4-A2)") (class "Default")
      (node (ref "J4") (pin "3") (pinfunction "A2_3") (pintype "passive"))
      (node (ref "U1") (pin "25") (pinfunction "PC2_25") (pintype "bidirectional"))
    )
    (net (code "31") (name "Net-(J4-A3)") (class "Default")
      (node (ref "J4") (pin "4") (pinfunction "A3_4") (pintype "passive"))
      (node (ref "U1") (pin "26") (pinfunction "PC3_26") (pintype "bidirectional"))
    )
    (net (code "32") (name "Net-(LED1-Pad2)") (class "Default")
      (node (ref "LED1") (pin "2") (pinfunction "2_2") (pintype "passive"))
      (node (ref "R2") (pin "2") (pinfunction "2_2") (pintype "passive"))
    )
    (net (code "33") (name "Net-(LED2-Pad1)") (class "Default")
      (node (ref "LED2") (pin "1") (pinfunction "1_1") (pintype "passive"))
      (node (ref "R1") (pin "1") (pinfunction "1_1") (pintype "passive"))
    )
    (net (code "34") (name "Net-(LED3-Pad2)") (class "Default")
      (node (ref "LED3") (pin "2") (pinfunction "2_2") (pintype "passive"))
      (node (ref "R3") (pin "2") (pinfunction "2_2") (pintype "passive"))
    )
    (net (code "35") (name "Net-(LED4-Pad2)") (class "Default")
      (node (ref "LED4") (pin "2") (pinfunction "2_2") (pintype "passive"))
      (node (ref "R5") (pin "2") (pinfunction "2_2") (pintype "passive"))
    )
    (net (code "36") (name "Net-(LED5-Pad2)") (class "Default")
      (node (ref "LED5") (pin "2") (pinfunction "2_2") (pintype "passive"))
      (node (ref "R7") (pin "2") (pinfunction "2_2") (pintype "passive"))
    )
    (net (code "37") (name "Net-(LED6-Pad2)") (class "Default")
      (node (ref "LED6") (pin "2") (pinfunction "2_2") (pintype "passive"))
      (node (ref "R8") (pin "2") (pinfunction "2_2") (pintype "passive"))
    )
    (net (code "38") (name "Net-(TP4-Sgn)") (class "Default")
      (node (ref "C7") (pin "2") (pinfunction "2_2") (pintype "passive"))
      (node (ref "R4") (pin "1") (pinfunction "1_1") (pintype "passive"))
      (node (ref "TP4") (pin "1") (pinfunction "Sgn_1") (pintype "passive"))
      (node (ref "U1") (pin "8") (pinfunction "PB7/XTAL2_8") (pintype "bidirectional"))
      (node (ref "Y1") (pin "3") (pinfunction "OSC_2_3") (pintype "passive"))
    )
    (net (code "39") (name "Net-(U1-AVCC)") (class "Default")
      (node (ref "C3") (pin "1") (pinfunction "1_1") (pintype "passive"))
      (node (ref "L1") (pin "2") (pinfunction "2_2") (pintype "passive"))
      (node (ref "U1") (pin "18") (pinfunction "AVCC_18") (pintype "power_in"))
    )
    (net (code "40") (name "Net-(U1-PB6{slash}XTAL1)") (class "Default")
      (node (ref "C5") (pin "2") (pinfunction "2_2") (pintype "passive"))
      (node (ref "R4") (pin "2") (pinfunction "2_2") (pintype "passive"))
      (node (ref "U1") (pin "7") (pinfunction "PB6/XTAL1_7") (pintype "bidirectional"))
      (node (ref "Y1") (pin "1") (pinfunction "OSC_1_1") (pintype "passive"))
    )
    (net (code "41") (name "Net-(U2-XI)") (class "Default")
      (node (ref "C11") (pin "2") (pinfunction "2_2") (pintype "passive"))
      (node (ref "R9") (pin "2") (pinfunction "2_2") (pintype "passive"))
      (node (ref "U2") (pin "7") (pinfunction "XI_7") (pintype "passive"))
      (node (ref "Y2") (pin "1") (pinfunction "OSC_1_1") (pintype "passive"))
    )
    (net (code "42") (name "Net-(U2-XO)") (class "Default")
      (node (ref "C12") (pin "2") (pinfunction "2_2") (pintype "passive"))
      (node (ref "R9") (pin "1") (pinfunction "1_1") (pintype "passive"))
      (node (ref "U2") (pin "8") (pinfunction "XO_8") (pintype "passive"))
      (node (ref "Y2") (pin "3") (pinfunction "OSC_2_3") (pintype "passive"))
    )
    (net (code "43") (name "unconnected-(D1-IO2-Pad2)") (class "Default")
      (node (ref "D1") (pin "2") (pinfunction "IO2_2") (pintype "passive"))
    )
    (net (code "44") (name "unconnected-(J1-IO-Pad2)") (class "Default")
      (node (ref "J1") (pin "2") (pinfunction "IO_2") (pintype "passive"))
    )
    (net (code "45") (name "unconnected-(J1-NC-Pad1)") (class "Default")
      (node (ref "J1") (pin "1") (pinfunction "NC_1") (pintype "passive"))
    )
    (net (code "46") (name "unconnected-(J5-ID-Pad4)") (class "Default")
      (node (ref "J5") (pin "4") (pinfunction "ID_4") (pintype "passive"))
    )
    (net (code "47") (name "unconnected-(U1-ADC6-Pad19)") (class "Default")
      (node (ref "U1") (pin "19") (pinfunction "ADC6_19") (pintype "bidirectional"))
    )
    (net (code "48") (name "unconnected-(U1-ADC7-Pad22)") (class "Default")
      (node (ref "U1") (pin "22") (pinfunction "ADC7_22") (pintype "bidirectional"))
    )
    (net (code "49") (name "unconnected-(U2-CTS#-Pad9)") (class "Default")
      (node (ref "U2") (pin "9") (pinfunction "CTS#_9") (pintype "passive"))
    )
    (net (code "50") (name "unconnected-(U2-DCD#-Pad12)") (class "Default")
      (node (ref "U2") (pin "12") (pinfunction "DCD#_12") (pintype "passive"))
    )
    (net (code "51") (name "unconnected-(U2-DSR#-Pad10)") (class "Default")
      (node (ref "U2") (pin "10") (pinfunction "DSR#_10") (pintype "passive"))
    )
    (net (code "52") (name "unconnected-(U2-RI#-Pad11)") (class "Default")
      (node (ref "U2") (pin "11") (pinfunction "RI#_11") (pintype "passive"))
    )
    (net (code "53") (name "unconnected-(U2-RS232-Pad15)") (class "Default")
      (node (ref "U2") (pin "15") (pinfunction "RS232_15") (pintype "passive"))
    )
    (net (code "54") (name "unconnected-(U2-RTS#-Pad14)") (class "Default")
      (node (ref "U2") (pin "14") (pinfunction "RTS#_14") (pintype "passive"))
    )
    (net (code "55") (name "unconnected-(U2-V3-Pad4)") (class "Default")
      (node (ref "U2") (pin "4") (pinfunction "V3_4") (pintype "passive"))
    )
  )
)
